# Full_Bridge_mk2_no_rectification.net
KiCad netlist of a schematic drawn in EAGLE
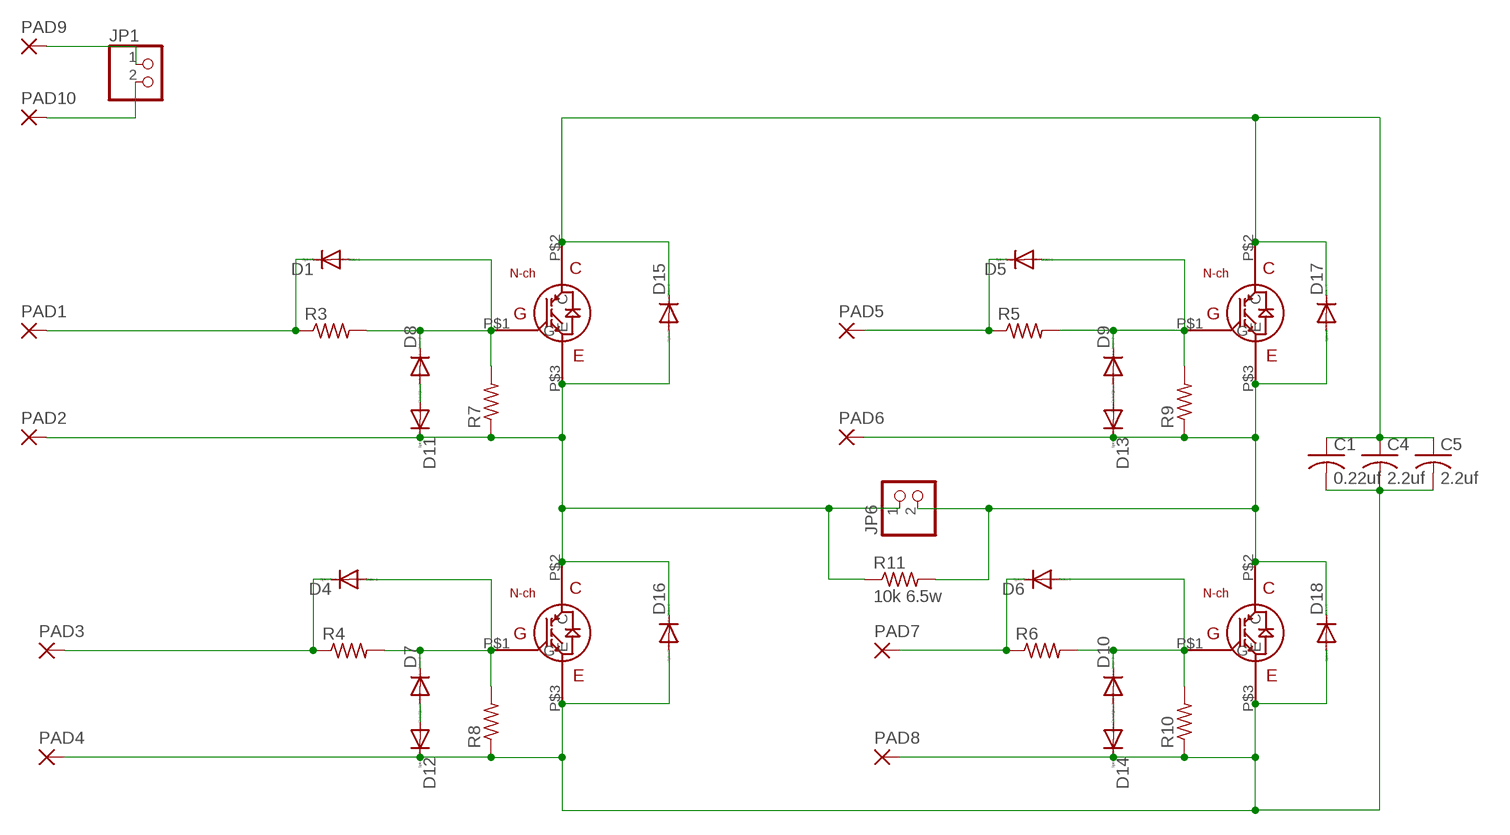
[diagram p0: schematic, sheet 1]

(export (version "E")
  (design (tool "Eeschema 10.0.6"))
  (components
    (comp (ref "C1")
      (value "0.22uf")
      (footprint "eagle-import:C375-155X418")
      (libsource (lib "eagle-import") (part "resistor_C-US375-155X418"))
    )
    (comp (ref "C4")
      (value "2.2uf")
      (footprint "eagle-import:C275-134X316")
      (libsource (lib "eagle-import") (part "C-US275-134X316"))
    )
    (comp (ref "C5")
      (value "2.2uf")
      (footprint "eagle-import:C275-134X316")
      (libsource (lib "eagle-import") (part "C-US275-134X316"))
    )
    (comp (ref "D1")
      (value "DIODE-DO-214AC")
      (footprint "eagle-import:DO-214AC")
      (libsource (lib "eagle-import") (part "DIODE-DO-214AC"))
    )
    (comp (ref "D4")
      (value "DIODE-DO-214AC")
      (footprint "eagle-import:DO-214AC")
      (libsource (lib "eagle-import") (part "DIODE-DO-214AC"))
    )
    (comp (ref "D5")
      (value "DIODE-DO-214AC")
      (footprint "eagle-import:DO-214AC")
      (libsource (lib "eagle-import") (part "DIODE-DO-214AC"))
    )
    (comp (ref "D6")
      (value "DIODE-DO-214AC")
      (footprint "eagle-import:DO-214AC")
      (libsource (lib "eagle-import") (part "DIODE-DO-214AC"))
    )
    (comp (ref "D7")
      (value "DIODE-DO-214AC")
      (footprint "eagle-import:DO-214AC")
      (libsource (lib "eagle-import") (part "DIODE-DO-214AC"))
    )
    (comp (ref "D8")
      (value "DIODE-DO-214AC")
      (footprint "eagle-import:DO-214AC")
      (libsource (lib "eagle-import") (part "DIODE-DO-214AC"))
    )
    (comp (ref "D9")
      (value "DIODE-DO-214AC")
      (footprint "eagle-import:DO-214AC")
      (libsource (lib "eagle-import") (part "DIODE-DO-214AC"))
    )
    (comp (ref "D10")
      (value "DIODE-DO-214AC")
      (footprint "eagle-import:DO-214AC")
      (libsource (lib "eagle-import") (part "DIODE-DO-214AC"))
    )
    (comp (ref "D11")
      (value "DIODE-DO-214AC")
      (footprint "eagle-import:DO-214AC")
      (libsource (lib "eagle-import") (part "DIODE-DO-214AC"))
    )
    (comp (ref "D12")
      (value "DIODE-DO-214AC")
      (footprint "eagle-import:DO-214AC")
      (libsource (lib "eagle-import") (part "DIODE-DO-214AC"))
    )
    (comp (ref "D13")
      (value "DIODE-DO-214AC")
      (footprint "eagle-import:DO-214AC")
      (libsource (lib "eagle-import") (part "DIODE-DO-214AC"))
    )
    (comp (ref "D14")
      (value "DIODE-DO-214AC")
      (footprint "eagle-import:DO-214AC")
      (libsource (lib "eagle-import") (part "DIODE-DO-214AC"))
    )
    (comp (ref "D15")
      (value "DIODE-DO201-15")
      (footprint "eagle-import:DO201-15")
      (libsource (lib "eagle-import") (part "DIODE-DO201-15"))
    )
    (comp (ref "D16")
      (value "DIODE-DO201-15")
      (footprint "eagle-import:DO201-15")
      (libsource (lib "eagle-import") (part "DIODE-DO201-15"))
    )
    (comp (ref "D17")
      (value "DIODE-DO201-15")
      (footprint "eagle-import:DO201-15")
      (libsource (lib "eagle-import") (part "DIODE-DO201-15"))
    )
    (comp (ref "D18")
      (value "DIODE-DO201-15")
      (footprint "eagle-import:DO201-15")
      (libsource (lib "eagle-import") (part "DIODE-DO201-15"))
    )
    (comp (ref "JP1")
      (value "PINHD-1X2")
      (footprint "eagle-import:1X02")
      (libsource (lib "eagle-import") (part "PINHD-1X2"))
    )
    (comp (ref "JP6")
      (value "PINHD-1X2-9.5")
      (footprint "eagle-import:1X02-9.5")
      (libsource (lib "eagle-import") (part "PINHD-1X2-9.5"))
    )
    (comp (ref "PAD1")
      (value "SMD5")
      (footprint "eagle-import:SMD2,54-5,08")
      (libsource (lib "eagle-import") (part "SMD5"))
    )
    (comp (ref "PAD2")
      (value "SMD5")
      (footprint "eagle-import:SMD2,54-5,08")
      (libsource (lib "eagle-import") (part "SMD5"))
    )
    (comp (ref "PAD3")
      (value "SMD5")
      (footprint "eagle-import:SMD2,54-5,08")
      (libsource (lib "eagle-import") (part "SMD5"))
    )
    (comp (ref "PAD4")
      (value "SMD5")
      (footprint "eagle-import:SMD2,54-5,08")
      (libsource (lib "eagle-import") (part "SMD5"))
    )
    (comp (ref "PAD5")
      (value "SMD5")
      (footprint "eagle-import:SMD2,54-5,08")
      (libsource (lib "eagle-import") (part "SMD5"))
    )
    (comp (ref "PAD6")
      (value "SMD5")
      (footprint "eagle-import:SMD2,54-5,08")
      (libsource (lib "eagle-import") (part "SMD5"))
    )
    (comp (ref "PAD7")
      (value "SMD5")
      (footprint "eagle-import:SMD2,54-5,08")
      (libsource (lib "eagle-import") (part "SMD5"))
    )
    (comp (ref "PAD8")
      (value "SMD5")
      (footprint "eagle-import:SMD2,54-5,08")
      (libsource (lib "eagle-import") (part "SMD5"))
    )
    (comp (ref "PAD9")
      (value "SMD5")
      (footprint "eagle-import:SMD2,54-5,08")
      (libsource (lib "eagle-import") (part "SMD5"))
    )
    (comp (ref "PAD10")
      (value "SMD5")
      (footprint "eagle-import:SMD2,54-5,08")
      (libsource (lib "eagle-import") (part "SMD5"))
    )
    (comp (ref "R3")
      (value "R-US_0207/10")
      (footprint "eagle-import:0207_10")
      (libsource (lib "eagle-import") (part "resistor_R-US_0207/10"))
    )
    (comp (ref "R4")
      (value "R-US_0207/10")
      (footprint "eagle-import:0207_10")
      (libsource (lib "eagle-import") (part "resistor_R-US_0207/10"))
    )
    (comp (ref "R5")
      (value "R-US_0207/10")
      (footprint "eagle-import:0207_10")
      (libsource (lib "eagle-import") (part "resistor_R-US_0207/10"))
    )
    (comp (ref "R6")
      (value "R-US_0207/10")
      (footprint "eagle-import:0207_10")
      (libsource (lib "eagle-import") (part "resistor_R-US_0207/10"))
    )
    (comp (ref "R7")
      (value "R-US_R0805")
      (footprint "eagle-import:R0805")
      (libsource (lib "eagle-import") (part "resistor_R-US_R0805"))
    )
    (comp (ref "R8")
      (value "R-US_R0805")
      (footprint "eagle-import:R0805")
      (libsource (lib "eagle-import") (part "resistor_R-US_R0805"))
    )
    (comp (ref "R9")
      (value "R-US_R0805")
      (footprint "eagle-import:R0805")
      (libsource (lib "eagle-import") (part "resistor_R-US_R0805"))
    )
    (comp (ref "R10")
      (value "R-US_R0805")
      (footprint "eagle-import:R0805")
      (libsource (lib "eagle-import") (part "resistor_R-US_R0805"))
    )
    (comp (ref "R11")
      (value "10k 6.5w")
      (footprint "eagle-import:P0817_22")
      (libsource (lib "eagle-import") (part "R-US_0817/22"))
    )
    (comp (ref "U$1")
      (value "TO-247B")
      (footprint "eagle-import:TO-247-FLATFIX")
      (libsource (lib "eagle-import") (part "TO-247B"))
    )
    (comp (ref "U$2")
      (value "TO-247B")
      (footprint "eagle-import:TO-247-FLATFIX")
      (libsource (lib "eagle-import") (part "TO-247B"))
    )
    (comp (ref "U$3")
      (value "TO-247B")
      (footprint "eagle-import:TO-247-FLATFIX")
      (libsource (lib "eagle-import") (part "TO-247B"))
    )
    (comp (ref "U$4")
      (value "TO-247B")
      (footprint "eagle-import:TO-247-FLATFIX")
      (libsource (lib "eagle-import") (part "TO-247B"))
    )
  )
  (nets
    (net (code "1") (name "Net-(D10-PadA)") (class "Default")
      (node (ref "D10") (pin "A") (pinfunction "A_A") (pintype "passive"))
      (node (ref "D14") (pin "A") (pinfunction "A_A") (pintype "passive"))
    )
    (net (code "2") (name "Net-(D11-PadA)") (class "Default")
      (node (ref "D11") (pin "A") (pinfunction "A_A") (pintype "passive"))
      (node (ref "D8") (pin "A") (pinfunction "A_A") (pintype "passive"))
    )
    (net (code "3") (name "Net-(D12-PadA)") (class "Default")
      (node (ref "D12") (pin "A") (pinfunction "A_A") (pintype "passive"))
      (node (ref "D7") (pin "A") (pinfunction "A_A") (pintype "passive"))
    )
    (net (code "4") (name "Net-(D13-PadA)") (class "Default")
      (node (ref "D13") (pin "A") (pinfunction "A_A") (pintype "passive"))
      (node (ref "D9") (pin "A") (pinfunction "A_A") (pintype "passive"))
    )
    (net (code "5") (name "Net-(PAD1-P)") (class "Default")
      (node (ref "D1") (pin "C") (pinfunction "C_C") (pintype "passive"))
      (node (ref "PAD1") (pin "1") (pinfunction "P_1") (pintype "passive"))
      (node (ref "R3") (pin "1") (pinfunction "1_1") (pintype "passive"))
    )
    (net (code "6") (name "Net-(PAD2-P)") (class "Default")
      (node (ref "D11") (pin "C") (pinfunction "C_C") (pintype "passive"))
      (node (ref "D15") (pin "A") (pinfunction "A_A") (pintype "passive"))
      (node (ref "D16") (pin "C") (pinfunction "C_C") (pintype "passive"))
      (node (ref "JP6") (pin "1") (pinfunction "1_1") (pintype "passive"))
      (node (ref "PAD2") (pin "1") (pinfunction "P_1") (pintype "passive"))
      (node (ref "R11") (pin "1") (pinfunction "1_1") (pintype "passive"))
      (node (ref "R7") (pin "1") (pinfunction "1_1") (pintype "passive"))
      (node (ref "U$1") (pin "P$3") (pinfunction "E_P$3") (pintype "bidirectional"))
      (node (ref "U$2") (pin "P$2") (pinfunction "C_P$2") (pintype "bidirectional"))
    )
    (net (code "7") (name "Net-(PAD3-P)") (class "Default")
      (node (ref "D4") (pin "C") (pinfunction "C_C") (pintype "passive"))
      (node (ref "PAD3") (pin "1") (pinfunction "P_1") (pintype "passive"))
      (node (ref "R4") (pin "1") (pinfunction "1_1") (pintype "passive"))
    )
    (net (code "8") (name "Net-(PAD4-P)") (class "Default")
      (node (ref "C1") (pin "2") (pinfunction "2_2") (pintype "passive"))
      (node (ref "C4") (pin "2") (pinfunction "2_2") (pintype "passive"))
      (node (ref "C5") (pin "2") (pinfunction "2_2") (pintype "passive"))
      (node (ref "D12") (pin "C") (pinfunction "C_C") (pintype "passive"))
      (node (ref "D14") (pin "C") (pinfunction "C_C") (pintype "passive"))
      (node (ref "D16") (pin "A") (pinfunction "A_A") (pintype "passive"))
      (node (ref "D18") (pin "A") (pinfunction "A_A") (pintype "passive"))
      (node (ref "PAD4") (pin "1") (pinfunction "P_1") (pintype "passive"))
      (node (ref "PAD8") (pin "1") (pinfunction "P_1") (pintype "passive"))
      (node (ref "R10") (pin "1") (pinfunction "1_1") (pintype "passive"))
      (node (ref "R8") (pin "1") (pinfunction "1_1") (pintype "passive"))
      (node (ref "U$2") (pin "P$3") (pinfunction "E_P$3") (pintype "bidirectional"))
      (node (ref "U$4") (pin "P$3") (pinfunction "E_P$3") (pintype "bidirectional"))
    )
    (net (code "9") (name "Net-(PAD5-P)") (class "Default")
      (node (ref "D5") (pin "C") (pinfunction "C_C") (pintype "passive"))
      (node (ref "PAD5") (pin "1") (pinfunction "P_1") (pintype "passive"))
      (node (ref "R5") (pin "1") (pinfunction "1_1") (pintype "passive"))
    )
    (net (code "10") (name "Net-(PAD6-P)") (class "Default")
      (node (ref "D13") (pin "C") (pinfunction "C_C") (pintype "passive"))
      (node (ref "D17") (pin "A") (pinfunction "A_A") (pintype "passive"))
      (node (ref "D18") (pin "C") (pinfunction "C_C") (pintype "passive"))
      (node (ref "JP6") (pin "2") (pinfunction "2_2") (pintype "passive"))
      (node (ref "PAD6") (pin "1") (pinfunction "P_1") (pintype "passive"))
      (node (ref "R11") (pin "2") (pinfunction "2_2") (pintype "passive"))
      (node (ref "R9") (pin "1") (pinfunction "1_1") (pintype "passive"))
      (node (ref "U$3") (pin "P$3") (pinfunction "E_P$3") (pintype "bidirectional"))
      (node (ref "U$4") (pin "P$2") (pinfunction "C_P$2") (pintype "bidirectional"))
    )
    (net (code "11") (name "Net-(PAD7-P)") (class "Default")
      (node (ref "D6") (pin "C") (pinfunction "C_C") (pintype "passive"))
      (node (ref "PAD7") (pin "1") (pinfunction "P_1") (pintype "passive"))
      (node (ref "R6") (pin "1") (pinfunction "1_1") (pintype "passive"))
    )
    (net (code "12") (name "Net-(PAD9-P)") (class "Default")
      (node (ref "JP1") (pin "1") (pinfunction "1_1") (pintype "passive"))
      (node (ref "PAD9") (pin "1") (pinfunction "P_1") (pintype "passive"))
    )
    (net (code "13") (name "Net-(PAD10-P)") (class "Default")
      (node (ref "JP1") (pin "2") (pinfunction "2_2") (pintype "passive"))
      (node (ref "PAD10") (pin "1") (pinfunction "P_1") (pintype "passive"))
    )
    (net (code "14") (name "Net-(U$1-C)") (class "Default")
      (node (ref "C1") (pin "1") (pinfunction "1_1") (pintype "passive"))
      (node (ref "C4") (pin "1") (pinfunction "1_1") (pintype "passive"))
      (node (ref "C5") (pin "1") (pinfunction "1_1") (pintype "passive"))
      (node (ref "D15") (pin "C") (pinfunction "C_C") (pintype "passive"))
      (node (ref "D17") (pin "C") (pinfunction "C_C") (pintype "passive"))
      (node (ref "U$1") (pin "P$2") (pinfunction "C_P$2") (pintype "bidirectional"))
      (node (ref "U$3") (pin "P$2") (pinfunction "C_P$2") (pintype "bidirectional"))
    )
    (net (code "15") (name "Net-(U$1-G)") (class "Default")
      (node (ref "D1") (pin "A") (pinfunction "A_A") (pintype "passive"))
      (node (ref "D8") (pin "C") (pinfunction "C_C") (pintype "passive"))
      (node (ref "R3") (pin "2") (pinfunction "2_2") (pintype "passive"))
      (node (ref "R7") (pin "2") (pinfunction "2_2") (pintype "passive"))
      (node (ref "U$1") (pin "P$1") (pinfunction "G_P$1") (pintype "bidirectional"))
    )
    (net (code "16") (name "Net-(U$2-G)") (class "Default")
      (node (ref "D4") (pin "A") (pinfunction "A_A") (pintype "passive"))
      (node (ref "D7") (pin "C") (pinfunction "C_C") (pintype "passive"))
      (node (ref "R4") (pin "2") (pinfunction "2_2") (pintype "passive"))
      (node (ref "R8") (pin "2") (pinfunction "2_2") (pintype "passive"))
      (node (ref "U$2") (pin "P$1") (pinfunction "G_P$1") (pintype "bidirectional"))
    )
    (net (code "17") (name "Net-(U$3-G)") (class "Default")
      (node (ref "D5") (pin "A") (pinfunction "A_A") (pintype "passive"))
      (node (ref "D9") (pin "C") (pinfunction "C_C") (pintype "passive"))
      (node (ref "R5") (pin "2") (pinfunction "2_2") (pintype "passive"))
      (node (ref "R9") (pin "2") (pinfunction "2_2") (pintype "passive"))
      (node (ref "U$3") (pin "P$1") (pinfunction "G_P$1") (pintype "bidirectional"))
    )
    (net (code "18") (name "Net-(U$4-G)") (class "Default")
      (node (ref "D10") (pin "C") (pinfunction "C_C") (pintype "passive"))
      (node (ref "D6") (pin "A") (pinfunction "A_A") (pintype "passive"))
      (node (ref "R10") (pin "2") (pinfunction "2_2") (pintype "passive"))
      (node (ref "R6") (pin "2") (pinfunction "2_2") (pintype "passive"))
      (node (ref "U$4") (pin "P$1") (pinfunction "G_P$1") (pintype "bidirectional"))
    )
  )
)
